# freaq3.net
KiCad netlist of a schematic drawn in EAGLE
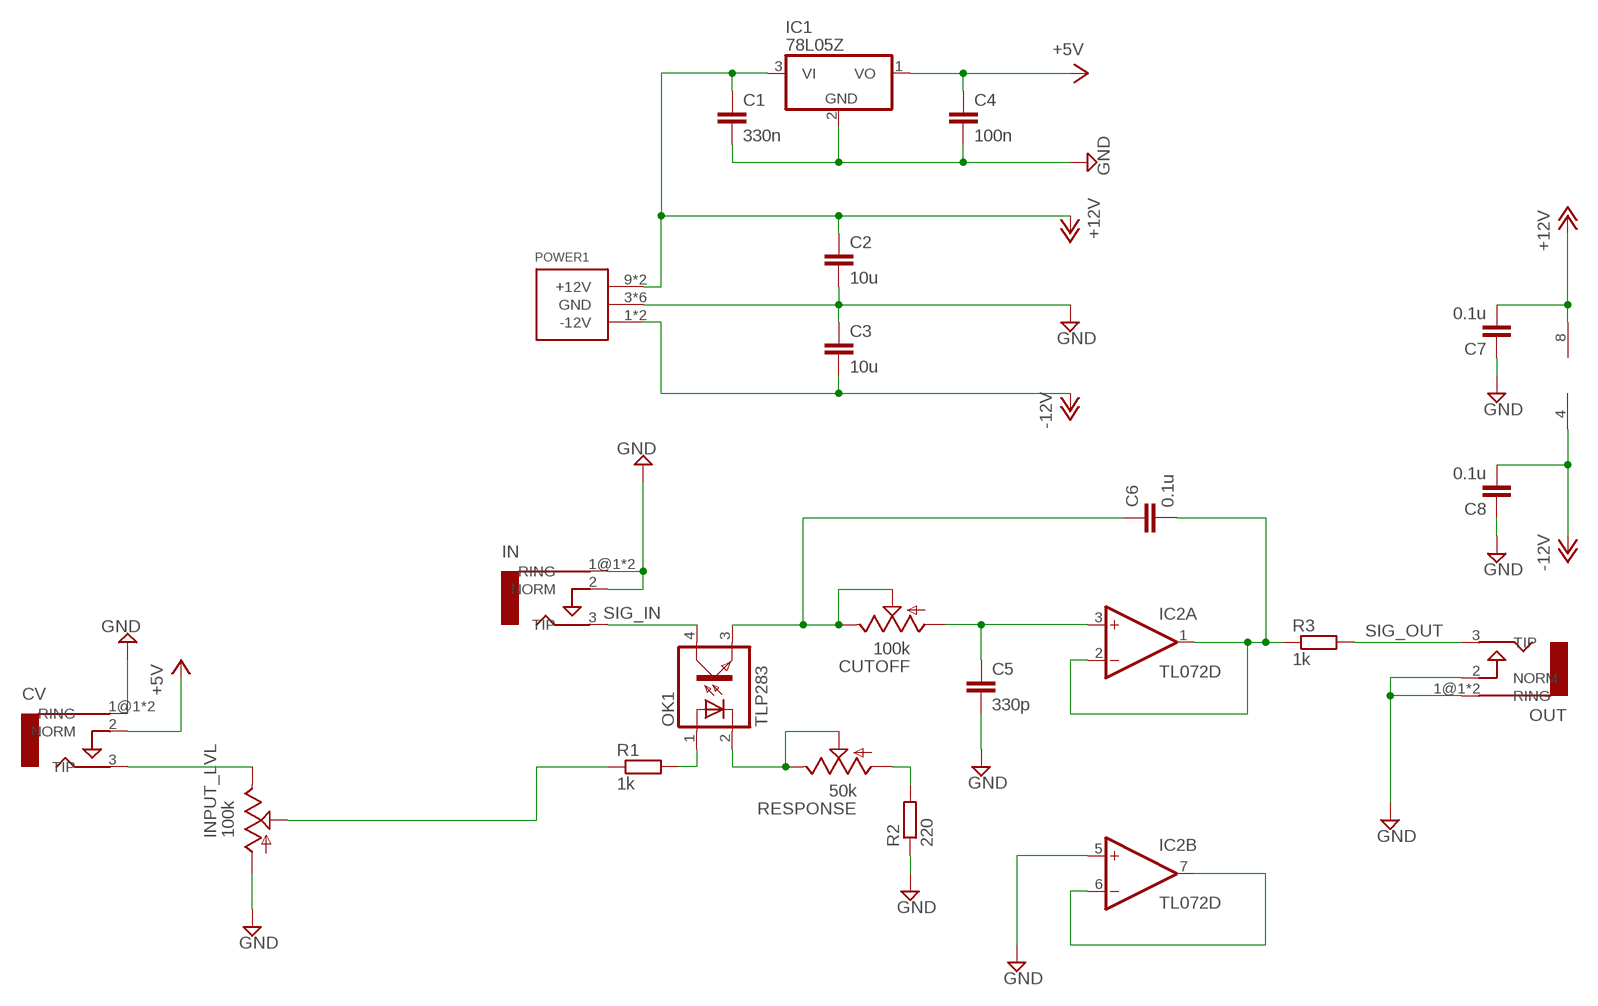
[diagram p0: schematic, sheet 1]

(export (version "E")
  (design (tool "Eeschema 10.0.6"))
  (components
    (comp (ref "C1")
      (value "330n")
      (footprint "eagle-import:C0805")
      (libsource (lib "eagle-import") (part "C-EUC0805"))
    )
    (comp (ref "C2")
      (value "10u")
      (footprint "eagle-import:C0805")
      (libsource (lib "eagle-import") (part "C-EUC0805"))
    )
    (comp (ref "C3")
      (value "10u")
      (footprint "eagle-import:C0805")
      (libsource (lib "eagle-import") (part "C-EUC0805"))
    )
    (comp (ref "C4")
      (value "100n")
      (footprint "eagle-import:C0805")
      (libsource (lib "eagle-import") (part "C-EUC0805"))
    )
    (comp (ref "C5")
      (value "330p")
      (footprint "eagle-import:C0805")
      (libsource (lib "eagle-import") (part "C-EUC0805"))
    )
    (comp (ref "C6")
      (value "0.1u")
      (footprint "eagle-import:C0805")
      (libsource (lib "eagle-import") (part "C-EUC0805"))
    )
    (comp (ref "C7")
      (value "0.1u")
      (footprint "eagle-import:C0805")
      (libsource (lib "eagle-import") (part "C-EUC0805"))
    )
    (comp (ref "C8")
      (value "0.1u")
      (footprint "eagle-import:C0805")
      (libsource (lib "eagle-import") (part "C-EUC0805"))
    )
    (comp (ref "CUTOFF")
      (value "100k")
      (footprint "eagle-import:9MM_SNAP-IN_POT")
      (libsource (lib "eagle-import") (part "9MM_SNAP-IN_POT_"))
    )
    (comp (ref "CV")
      (value "AUDIO-JACKERTHENVAR")
      (footprint "eagle-import:ERTHENVAR-JACK")
      (libsource (lib "eagle-import") (part "AUDIO-JACKERTHENVAR"))
    )
    (comp (ref "IC1")
      (value "78L05Z")
      (footprint "eagle-import:TO92")
      (libsource (lib "eagle-import") (part "78ZL05"))
    )
    (comp (ref "IC2")
      (value "TL072D")
      (footprint "eagle-import:SO08")
      (libsource (lib "eagle-import") (part "TL072D"))
    )
    (comp (ref "IN")
      (value "AUDIO-JACKERTHENVAR")
      (footprint "eagle-import:ERTHENVAR-JACK")
      (libsource (lib "eagle-import") (part "AUDIO-JACKERTHENVAR"))
    )
    (comp (ref "INPUT_LVL")
      (value "100k")
      (footprint "eagle-import:9MM_SNAP-IN_POT")
      (libsource (lib "eagle-import") (part "9MM_SNAP-IN_POT_"))
    )
    (comp (ref "OK1")
      (value "TLP283")
      (footprint "eagle-import:MINI-FLAT-4")
      (libsource (lib "eagle-import") (part "TLP283"))
    )
    (comp (ref "OUT")
      (value "AUDIO-JACKERTHENVAR")
      (footprint "eagle-import:ERTHENVAR-JACK")
      (libsource (lib "eagle-import") (part "AUDIO-JACKERTHENVAR"))
    )
    (comp (ref "POWER1")
      (value "POWER_SIMPLE10")
      (footprint "eagle-import:POWER_10")
      (libsource (lib "eagle-import") (part "POWER_SIMPLE10"))
    )
    (comp (ref "R1")
      (value "1k")
      (footprint "eagle-import:R0805")
      (libsource (lib "eagle-import") (part "R-EU_R0805"))
    )
    (comp (ref "R2")
      (value "220")
      (footprint "eagle-import:R0805")
      (libsource (lib "eagle-import") (part "R-EU_R0805"))
    )
    (comp (ref "R3")
      (value "1k")
      (footprint "eagle-import:R0805")
      (libsource (lib "eagle-import") (part "R-EU_R0805"))
    )
    (comp (ref "RESPONSE")
      (value "50k")
      (footprint "eagle-import:9MM_SNAP-IN_POT")
      (libsource (lib "eagle-import") (part "9MM_SNAP-IN_POT_"))
    )
  )
  (nets
    (net (code "1") (name "+5V") (class "Default")
      (node (ref "C4") (pin "1") (pinfunction "1_1") (pintype "passive"))
      (node (ref "CV") (pin "2") (pinfunction "NORM_2") (pintype "bidirectional"))
      (node (ref "IC1") (pin "1") (pinfunction "VO_1") (pintype "passive"))
    )
    (net (code "2") (name "+12V") (class "Default")
      (node (ref "C1") (pin "1") (pinfunction "1_1") (pintype "passive"))
      (node (ref "C2") (pin "1") (pinfunction "1_1") (pintype "passive"))
      (node (ref "C7") (pin "2") (pinfunction "2_2") (pintype "passive"))
      (node (ref "IC1") (pin "3") (pinfunction "VI_3") (pintype "input"))
      (node (ref "IC2") (pin "8") (pinfunction "V+_8") (pintype "power_in"))
      (node (ref "POWER1") (pin "10") (pinfunction "+12V_10") (pintype "bidirectional"))
      (node (ref "POWER1") (pin "9") (pinfunction "+12V_9") (pintype "bidirectional"))
    )
    (net (code "3") (name "-12V") (class "Default")
      (node (ref "C3") (pin "2") (pinfunction "2_2") (pintype "passive"))
      (node (ref "C8") (pin "2") (pinfunction "2_2") (pintype "passive"))
      (node (ref "IC2") (pin "4") (pinfunction "V-_4") (pintype "power_in"))
      (node (ref "POWER1") (pin "1") (pinfunction "-12V_1") (pintype "bidirectional"))
      (node (ref "POWER1") (pin "2") (pinfunction "-12V_2") (pintype "bidirectional"))
    )
    (net (code "4") (name "/SIG_IN") (class "Default")
      (node (ref "IN") (pin "3") (pinfunction "TIP_3") (pintype "bidirectional"))
      (node (ref "OK1") (pin "4") (pinfunction "COL_4") (pintype "passive"))
    )
    (net (code "5") (name "/SIG_OUT") (class "Default")
      (node (ref "OUT") (pin "3") (pinfunction "TIP_3") (pintype "bidirectional"))
      (node (ref "R3") (pin "2") (pinfunction "2_2") (pintype "passive"))
    )
    (net (code "6") (name "GND") (class "Default")
      (node (ref "C1") (pin "2") (pinfunction "2_2") (pintype "passive"))
      (node (ref "C2") (pin "2") (pinfunction "2_2") (pintype "passive"))
      (node (ref "C3") (pin "1") (pinfunction "1_1") (pintype "passive"))
      (node (ref "C4") (pin "2") (pinfunction "2_2") (pintype "passive"))
      (node (ref "C5") (pin "2") (pinfunction "2_2") (pintype "passive"))
      (node (ref "C7") (pin "1") (pinfunction "1_1") (pintype "passive"))
      (node (ref "C8") (pin "1") (pinfunction "1_1") (pintype "passive"))
      (node (ref "CV") (pin "1@1") (pinfunction "RING_1@1") (pintype "bidirectional"))
      (node (ref "CV") (pin "1@2") (pinfunction "RING_1@2") (pintype "bidirectional"))
      (node (ref "IC1") (pin "2") (pinfunction "GND_2") (pintype "passive"))
      (node (ref "IC2") (pin "5") (pinfunction "+IN_5") (pintype "input"))
      (node (ref "IN") (pin "1@1") (pinfunction "RING_1@1") (pintype "bidirectional"))
      (node (ref "IN") (pin "1@2") (pinfunction "RING_1@2") (pintype "bidirectional"))
      (node (ref "IN") (pin "2") (pinfunction "NORM_2") (pintype "bidirectional"))
      (node (ref "INPUT_LVL") (pin "1") (pinfunction "A_1") (pintype "passive"))
      (node (ref "OUT") (pin "1@1") (pinfunction "RING_1@1") (pintype "bidirectional"))
      (node (ref "OUT") (pin "1@2") (pinfunction "RING_1@2") (pintype "bidirectional"))
      (node (ref "OUT") (pin "2") (pinfunction "NORM_2") (pintype "bidirectional"))
      (node (ref "POWER1") (pin "3") (pinfunction "GND_3") (pintype "bidirectional"))
      (node (ref "POWER1") (pin "4") (pinfunction "GND_4") (pintype "bidirectional"))
      (node (ref "POWER1") (pin "5") (pinfunction "GND_5") (pintype "bidirectional"))
      (node (ref "POWER1") (pin "6") (pinfunction "GND_6") (pintype "bidirectional"))
      (node (ref "POWER1") (pin "7") (pinfunction "GND_7") (pintype "bidirectional"))
      (node (ref "POWER1") (pin "8") (pinfunction "GND_8") (pintype "bidirectional"))
      (node (ref "R2") (pin "1") (pinfunction "1_1") (pintype "passive"))
    )
    (net (code "7") (name "Net-(CUTOFF-A)") (class "Default")
      (node (ref "C5") (pin "1") (pinfunction "1_1") (pintype "passive"))
      (node (ref "CUTOFF") (pin "1") (pinfunction "A_1") (pintype "passive"))
      (node (ref "IC2") (pin "3") (pinfunction "+IN_3") (pintype "input"))
    )
    (net (code "8") (name "Net-(CUTOFF-E)") (class "Default")
      (node (ref "C6") (pin "1") (pinfunction "1_1") (pintype "passive"))
      (node (ref "CUTOFF") (pin "2") (pinfunction "S_2") (pintype "passive"))
      (node (ref "CUTOFF") (pin "3") (pinfunction "E_3") (pintype "passive"))
      (node (ref "OK1") (pin "3") (pinfunction "EMIT_3") (pintype "passive"))
    )
    (net (code "9") (name "Net-(CV-TIP)") (class "Default")
      (node (ref "CV") (pin "3") (pinfunction "TIP_3") (pintype "bidirectional"))
      (node (ref "INPUT_LVL") (pin "3") (pinfunction "E_3") (pintype "passive"))
    )
    (net (code "10") (name "Net-(IC2A--IN)") (class "Default")
      (node (ref "C6") (pin "2") (pinfunction "2_2") (pintype "passive"))
      (node (ref "IC2") (pin "1") (pinfunction "OUT_1") (pintype "output"))
      (node (ref "IC2") (pin "2") (pinfunction "-IN_2") (pintype "input"))
      (node (ref "R3") (pin "1") (pinfunction "1_1") (pintype "passive"))
    )
    (net (code "11") (name "Net-(IC2B--IN)") (class "Default")
      (node (ref "IC2") (pin "6") (pinfunction "-IN_6") (pintype "input"))
      (node (ref "IC2") (pin "7") (pinfunction "OUT_7") (pintype "output"))
    )
    (net (code "12") (name "Net-(INPUT_LVL-S)") (class "Default")
      (node (ref "INPUT_LVL") (pin "2") (pinfunction "S_2") (pintype "passive"))
      (node (ref "R1") (pin "1") (pinfunction "1_1") (pintype "passive"))
    )
    (net (code "13") (name "Net-(OK1-A)") (class "Default")
      (node (ref "OK1") (pin "1") (pinfunction "A_1") (pintype "passive"))
      (node (ref "R1") (pin "2") (pinfunction "2_2") (pintype "passive"))
    )
    (net (code "14") (name "Net-(OK1-C)") (class "Default")
      (node (ref "OK1") (pin "2") (pinfunction "C_2") (pintype "passive"))
      (node (ref "RESPONSE") (pin "2") (pinfunction "S_2") (pintype "passive"))
      (node (ref "RESPONSE") (pin "3") (pinfunction "E_3") (pintype "passive"))
    )
    (net (code "15") (name "Net-(RESPONSE-A)") (class "Default")
      (node (ref "R2") (pin "2") (pinfunction "2_2") (pintype "passive"))
      (node (ref "RESPONSE") (pin "1") (pinfunction "A_1") (pintype "passive"))
    )
  )
)
